# ProDoc_Schematic1_2024-09-24.net
KiCad netlist of a schematic drawn in EasyEDA Pro
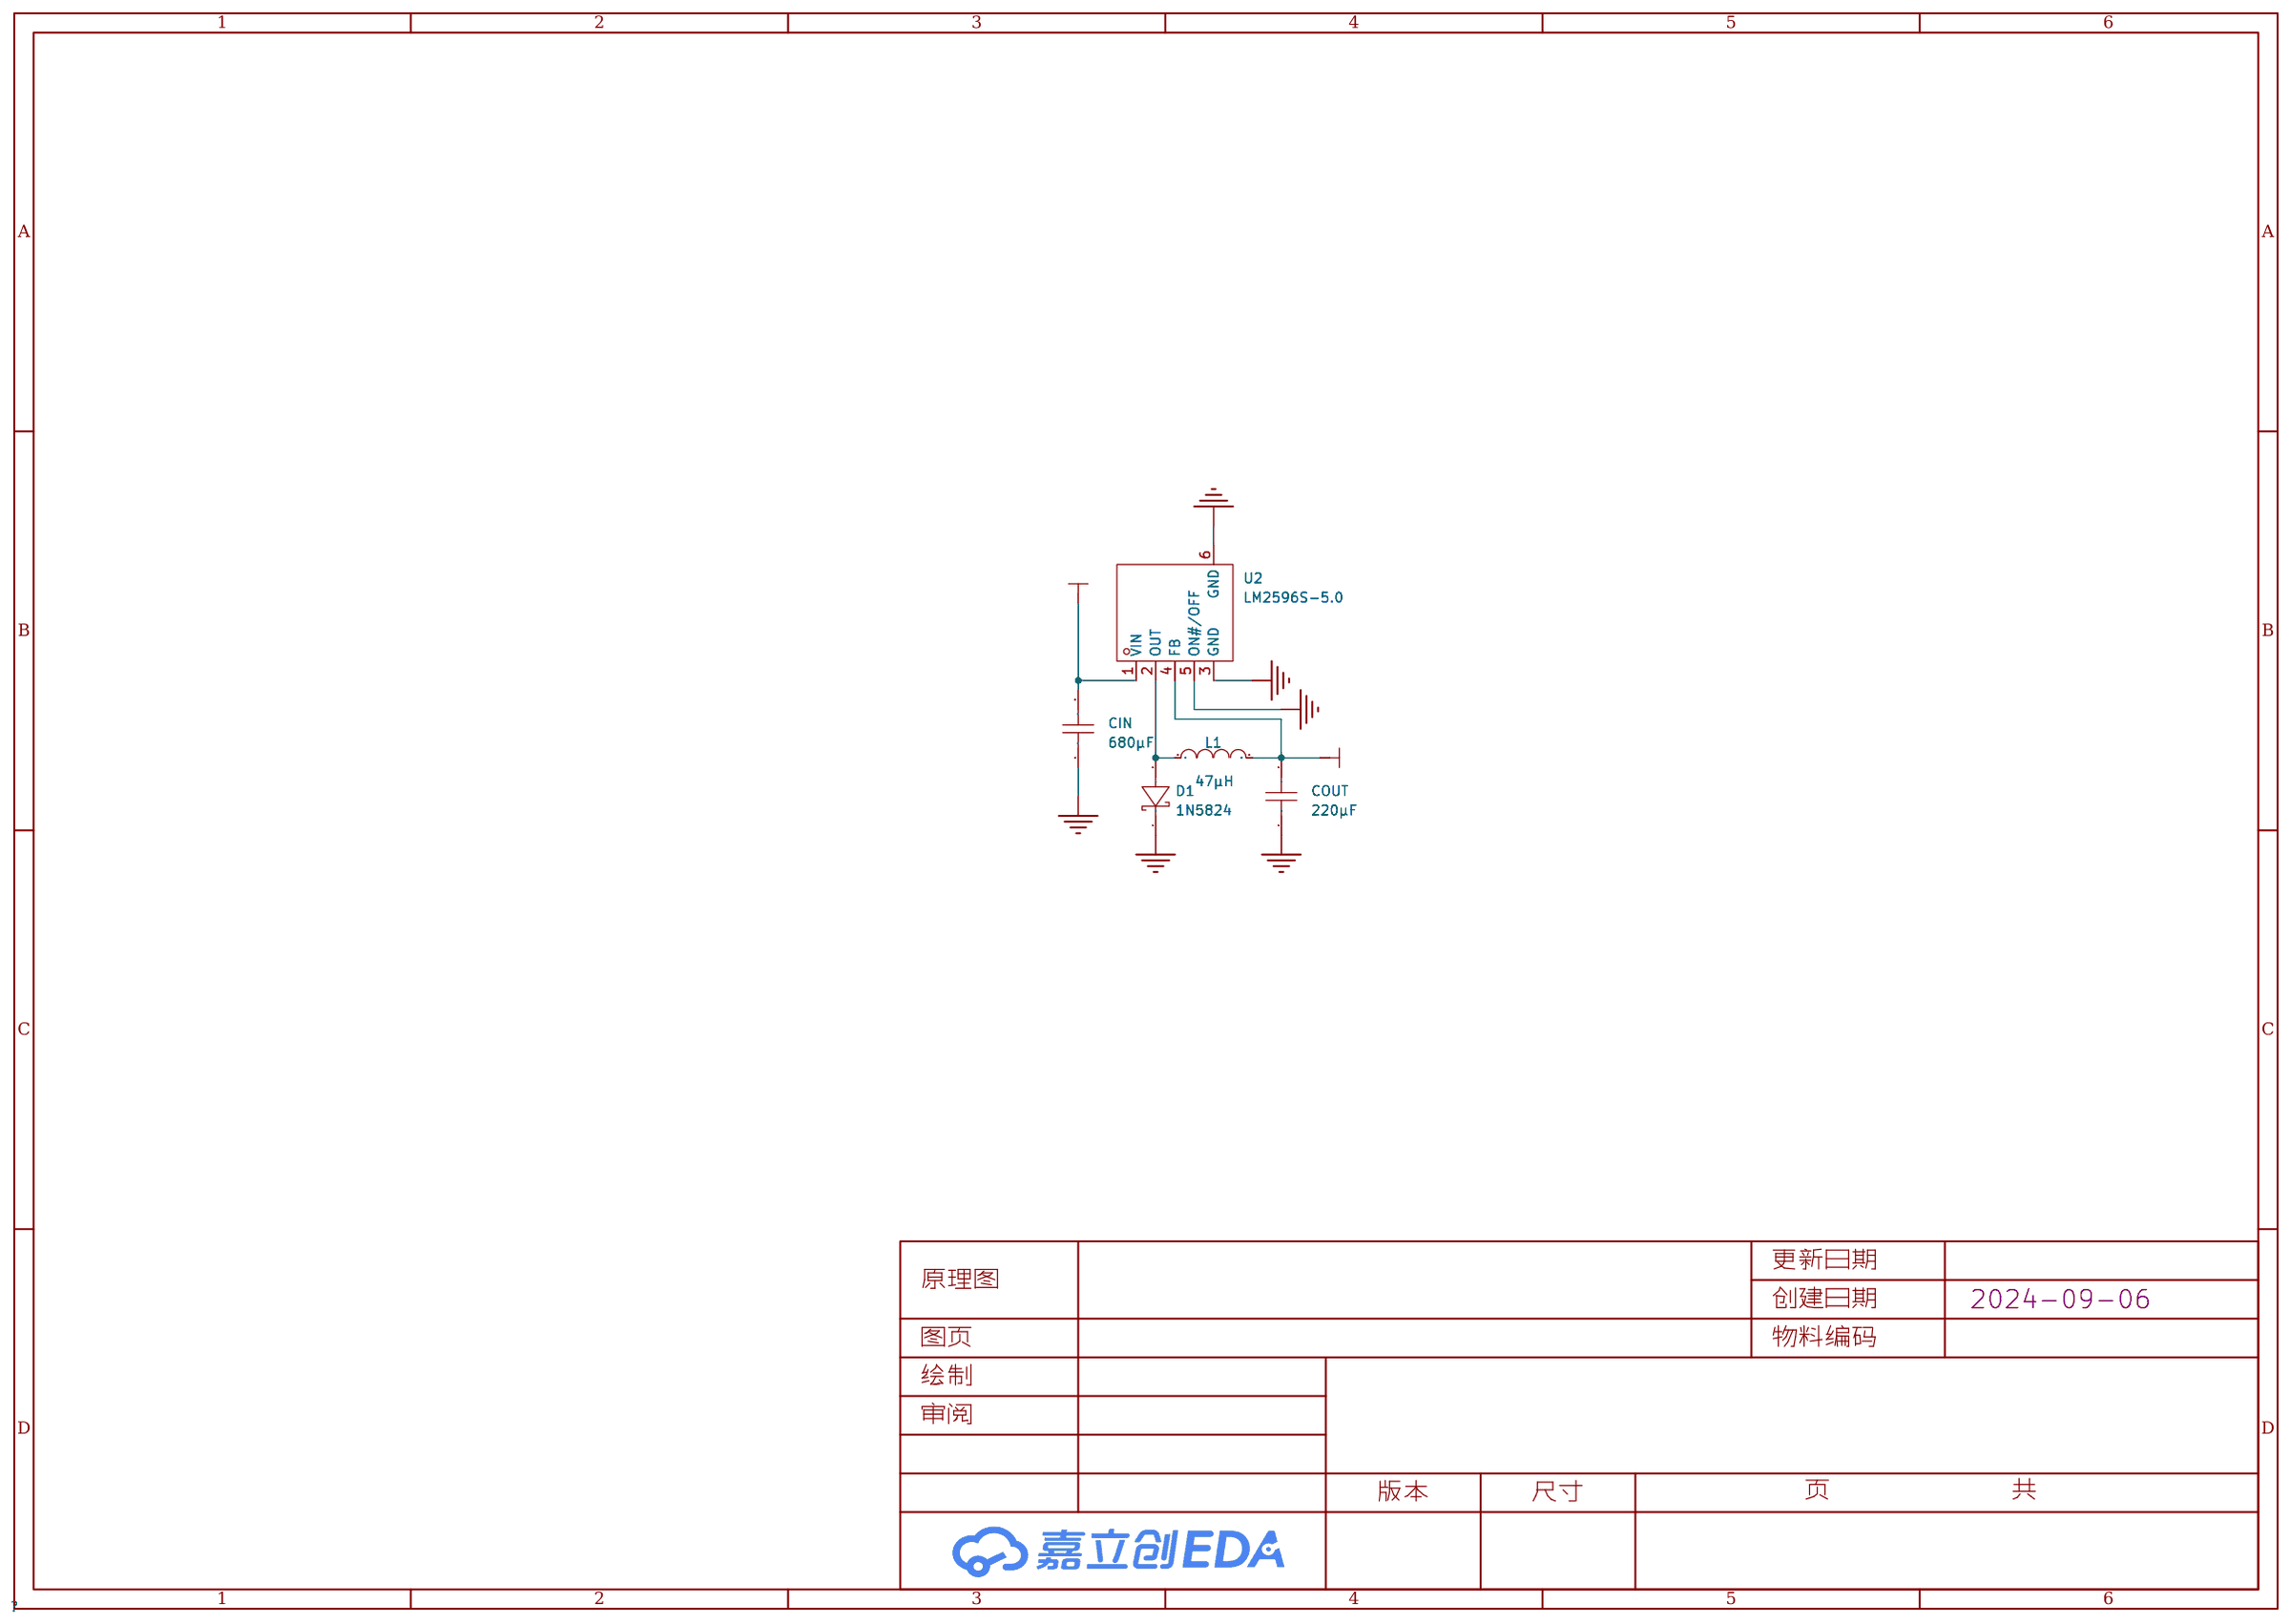
[diagram p0: schematic sheet]

(export (version "E")
  (design (tool "Eeschema 10.0.6"))
  (components
    (comp (ref "CIN")
      (value "680μF")
      (footprint "easyedapro:C0603")
      (libsource (lib "easyedapro") (part "CapAcitance"))
    )
    (comp (ref "COUT")
      (value "220μF")
      (footprint "easyedapro:C0603")
      (libsource (lib "easyedapro") (part "CapAcitance"))
    )
    (comp (ref "D1")
      (value "1N5824")
      (footprint "easyedapro:DO-27_BD5.3-L8.4-P12.40-D1.3-RD")
      (description "二极管配置:独立式;正向压降(Vf):550mV@5A;直流反向耐压(Vr):30V;平均整流电流(Io):5A;")
      (fields (field (name "Manufacturer") "FUXINSEMI(富芯森美)"))
      (libsource (lib "easyedapro") (part "1N5824_C7503125"))
    )
    (comp (ref "L1")
      (value "47μH")
      (footprint "easyedapro:L0603")
      (libsource (lib "easyedapro") (part "SDFL1608S100KTF"))
    )
    (comp (ref "U2")
      (value "LM2596S-5.0")
      (footprint "easyedapro:TO-263-5_L10.1-W8.7-P1.70-LS15.2-BR")
      (description "功能类型：降压型 输出类型：固定 输入电压：40V 输出电压：5V 输出电流(最大值)：3A")
      (fields (field (name "Manufacturer") "TWGMC(台湾迪嘉)"))
      (libsource (lib "easyedapro") (part "LM2596S-5.0_C5276750"))
    )
  )
  (nets
    (net (code "1") (name "5V") (class "Default")
      (node (ref "COUT") (pin "2") (pinfunction "2_2") (pintype "input"))
      (node (ref "L1") (pin "2") (pinfunction "2_2") (pintype "unspecified"))
      (node (ref "U2") (pin "4") (pinfunction "FB_4") (pintype "unspecified"))
    )
    (net (code "2") (name "24V") (class "Default")
      (node (ref "CIN") (pin "2") (pinfunction "2_2") (pintype "input"))
      (node (ref "U2") (pin "1") (pinfunction "VIN_1") (pintype "unspecified"))
    )
    (net (code "3") (name "GND") (class "Default")
      (node (ref "CIN") (pin "1") (pinfunction "1_1") (pintype "input"))
      (node (ref "COUT") (pin "1") (pinfunction "1_1") (pintype "input"))
      (node (ref "D1") (pin "1") (pinfunction "K_1") (pintype "unspecified"))
      (node (ref "U2") (pin "3") (pinfunction "GND_3") (pintype "unspecified"))
      (node (ref "U2") (pin "5") (pinfunction "ON#/OFF_5") (pintype "unspecified"))
      (node (ref "U2") (pin "6") (pinfunction "GND_6") (pintype "unspecified"))
    )
    (net (code "4") (name "Net-(D1-A)") (class "Default")
      (node (ref "D1") (pin "2") (pinfunction "A_2") (pintype "unspecified"))
      (node (ref "L1") (pin "1") (pinfunction "1_1") (pintype "unspecified"))
      (node (ref "U2") (pin "2") (pinfunction "OUT_2") (pintype "unspecified"))
    )
  )
)
